# CRUVI.net
KiCad netlist of a schematic drawn in Altium Designer
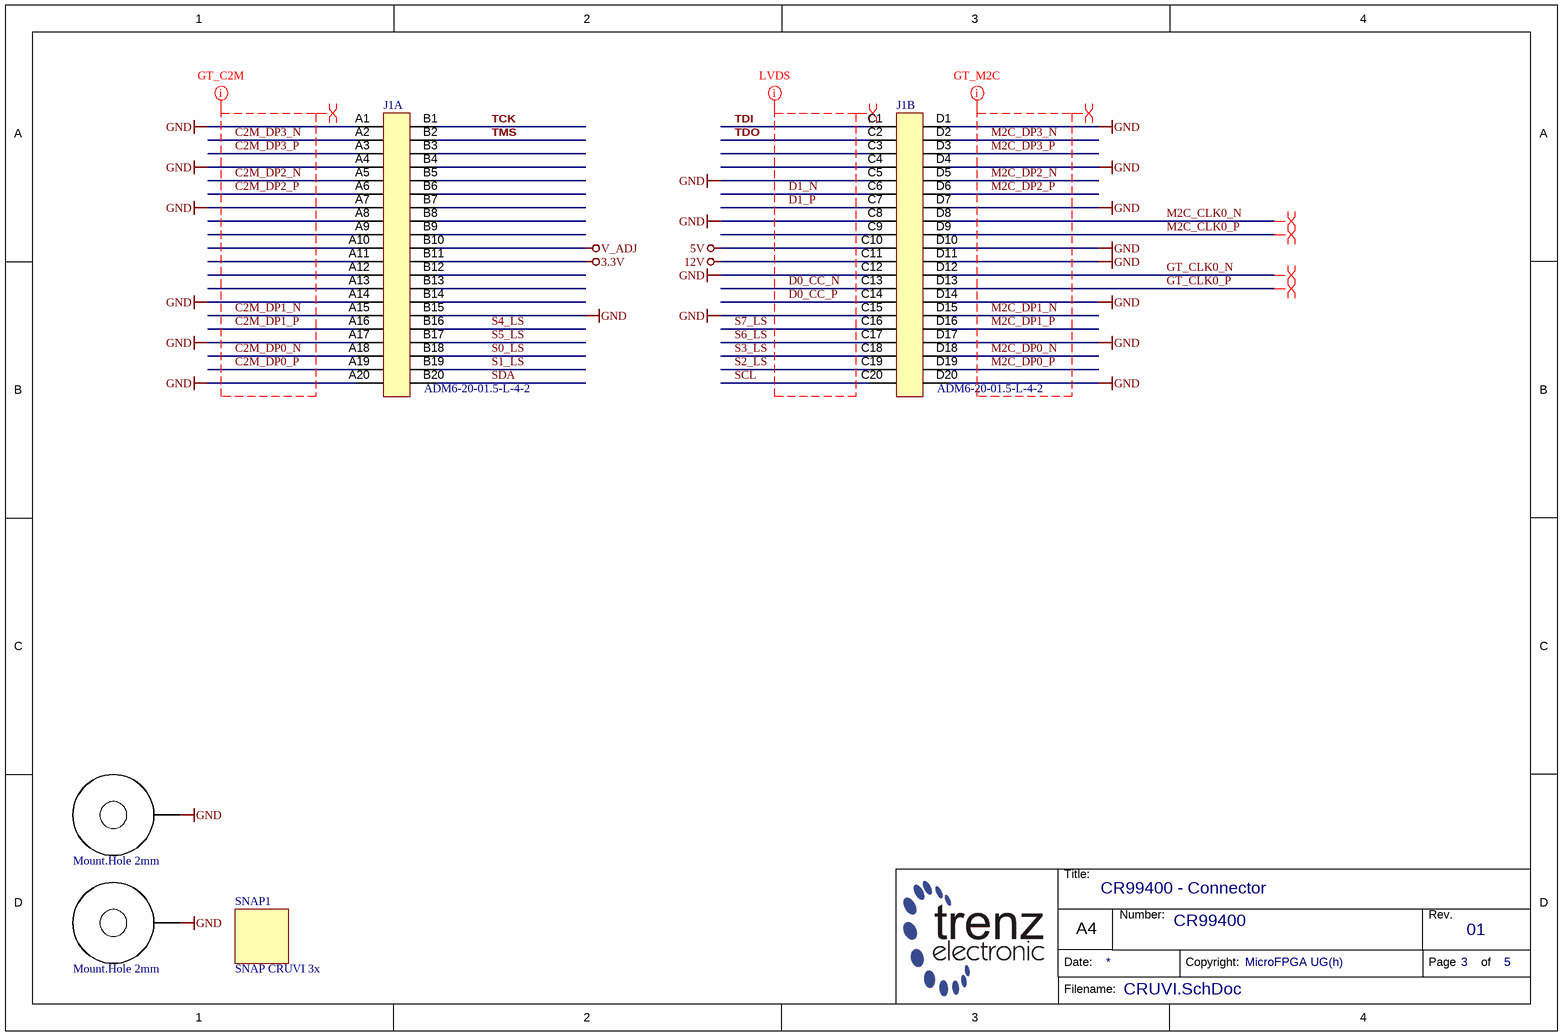
[diagram p0: CRUVI.SchDoc]

(export (version "E")
  (design (tool "Eeschema 10.0.6"))
  (components
    (comp (ref "H1")
      (value "Mount.Hole 2mm")
      (footprint "MHole2_2mm")
      (description "Mounting Hole 2mm Plated (Custom)")
      (libsource (lib "TE") (part "MHole"))
    )
    (comp (ref "H2")
      (value "Mount.Hole 2mm")
      (footprint "MHole2_2mm")
      (description "Mounting Hole 2mm Plated (Custom)")
      (libsource (lib "TE") (part "MHole"))
    )
    (comp (ref "J1")
      (value "ADM6-20-01.5-L-4-2")
      (footprint "ADM6-20-01.5-L-4-2")
      (fields (field (name "VOLTAGE") "155 VAC"))
      (libsource (lib "TE") (part "CON-20-A-D"))
    )
    (comp (ref "SNAP1")
      (value "SNAP CRUVI 3x")
      (footprint "CRUVI_3x_Snap")
      (description "SNAP for CRUVI 3x")
      (libsource (lib "TE") (part "DUMMY_NO_BOM"))
    )
  )
  (nets
    (net (code "1") (name "/C2M_DP0_N") (class "Default")
      (node (ref "J1") (pin "A18") (pinfunction "A18_A18") (pintype "passive"))
    )
    (net (code "2") (name "/C2M_DP0_P") (class "Default")
      (node (ref "J1") (pin "A19") (pinfunction "A19_A19") (pintype "passive"))
    )
    (net (code "3") (name "/C2M_DP1_N") (class "Default")
      (node (ref "J1") (pin "A15") (pinfunction "A15_A15") (pintype "passive"))
    )
    (net (code "4") (name "/C2M_DP1_P") (class "Default")
      (node (ref "J1") (pin "A16") (pinfunction "A16_A16") (pintype "passive"))
    )
    (net (code "5") (name "/C2M_DP2_N") (class "Default")
      (node (ref "J1") (pin "A5") (pinfunction "A5_A5") (pintype "passive"))
    )
    (net (code "6") (name "/C2M_DP2_P") (class "Default")
      (node (ref "J1") (pin "A6") (pinfunction "A6_A6") (pintype "passive"))
    )
    (net (code "7") (name "/C2M_DP3_N") (class "Default")
      (node (ref "J1") (pin "A2") (pinfunction "A2_A2") (pintype "passive"))
    )
    (net (code "8") (name "/C2M_DP3_P") (class "Default")
      (node (ref "J1") (pin "A3") (pinfunction "A3_A3") (pintype "passive"))
    )
    (net (code "9") (name "/D0_CC_N") (class "Default")
      (node (ref "J1") (pin "C13") (pinfunction "C13_C13") (pintype "passive"))
    )
    (net (code "10") (name "/D0_CC_P") (class "Default")
      (node (ref "J1") (pin "C14") (pinfunction "C14_C14") (pintype "passive"))
    )
    (net (code "11") (name "/D1_N") (class "Default")
      (node (ref "J1") (pin "C6") (pinfunction "C6_C6") (pintype "passive"))
    )
    (net (code "12") (name "/D1_P") (class "Default")
      (node (ref "J1") (pin "C7") (pinfunction "C7_C7") (pintype "passive"))
    )
    (net (code "13") (name "/GT_CLK0_N") (class "Default")
      (node (ref "J1") (pin "D12") (pinfunction "D12_D12") (pintype "passive"))
    )
    (net (code "14") (name "/GT_CLK0_P") (class "Default")
      (node (ref "J1") (pin "D13") (pinfunction "D13_D13") (pintype "passive"))
    )
    (net (code "15") (name "/M2C_CLK0_N") (class "Default")
      (node (ref "J1") (pin "D8") (pinfunction "D8_D8") (pintype "passive"))
    )
    (net (code "16") (name "/M2C_CLK0_P") (class "Default")
      (node (ref "J1") (pin "D9") (pinfunction "D9_D9") (pintype "passive"))
    )
    (net (code "17") (name "/M2C_DP0_N") (class "Default")
      (node (ref "J1") (pin "D18") (pinfunction "D18_D18") (pintype "passive"))
    )
    (net (code "18") (name "/M2C_DP0_P") (class "Default")
      (node (ref "J1") (pin "D19") (pinfunction "D19_D19") (pintype "passive"))
    )
    (net (code "19") (name "/M2C_DP1_N") (class "Default")
      (node (ref "J1") (pin "D15") (pinfunction "D15_D15") (pintype "passive"))
    )
    (net (code "20") (name "/M2C_DP1_P") (class "Default")
      (node (ref "J1") (pin "D16") (pinfunction "D16_D16") (pintype "passive"))
    )
    (net (code "21") (name "/M2C_DP2_N") (class "Default")
      (node (ref "J1") (pin "D5") (pinfunction "D5_D5") (pintype "passive"))
    )
    (net (code "22") (name "/M2C_DP2_P") (class "Default")
      (node (ref "J1") (pin "D6") (pinfunction "D6_D6") (pintype "passive"))
    )
    (net (code "23") (name "/M2C_DP3_N") (class "Default")
      (node (ref "J1") (pin "D2") (pinfunction "D2_D2") (pintype "passive"))
    )
    (net (code "24") (name "/M2C_DP3_P") (class "Default")
      (node (ref "J1") (pin "D3") (pinfunction "D3_D3") (pintype "passive"))
    )
    (net (code "25") (name "/S0_LS") (class "Default")
      (node (ref "J1") (pin "B18") (pinfunction "B18_B18") (pintype "passive"))
    )
    (net (code "26") (name "/S1_LS") (class "Default")
      (node (ref "J1") (pin "B19") (pinfunction "B19_B19") (pintype "passive"))
    )
    (net (code "27") (name "/S2_LS") (class "Default")
      (node (ref "J1") (pin "C19") (pinfunction "C19_C19") (pintype "passive"))
    )
    (net (code "28") (name "/S3_LS") (class "Default")
      (node (ref "J1") (pin "C18") (pinfunction "C18_C18") (pintype "passive"))
    )
    (net (code "29") (name "/S4_LS") (class "Default")
      (node (ref "J1") (pin "B16") (pinfunction "B16_B16") (pintype "passive"))
    )
    (net (code "30") (name "/S5_LS") (class "Default")
      (node (ref "J1") (pin "B17") (pinfunction "B17_B17") (pintype "passive"))
    )
    (net (code "31") (name "/S6_LS") (class "Default")
      (node (ref "J1") (pin "C17") (pinfunction "C17_C17") (pintype "passive"))
    )
    (net (code "32") (name "/S7_LS") (class "Default")
      (node (ref "J1") (pin "C16") (pinfunction "C16_C16") (pintype "passive"))
    )
    (net (code "33") (name "/SCL") (class "Default")
      (node (ref "J1") (pin "C20") (pinfunction "C20_C20") (pintype "passive"))
    )
    (net (code "34") (name "/SDA") (class "Default")
      (node (ref "J1") (pin "B20") (pinfunction "B20_B20") (pintype "passive"))
    )
    (net (code "35") (name "/TCK") (class "Default")
      (node (ref "J1") (pin "B1") (pinfunction "B1_B1") (pintype "passive"))
    )
    (net (code "36") (name "/TDI") (class "Default")
      (node (ref "J1") (pin "C1") (pinfunction "C1_C1") (pintype "passive"))
    )
    (net (code "37") (name "/TDO") (class "Default")
      (node (ref "J1") (pin "C2") (pinfunction "C2_C2") (pintype "passive"))
    )
    (net (code "38") (name "/TMS") (class "Default")
      (node (ref "J1") (pin "B2") (pinfunction "B2_B2") (pintype "passive"))
    )
    (net (code "39") (name "3.3V") (class "Default")
      (node (ref "J1") (pin "B11") (pinfunction "B11_B11") (pintype "passive"))
    )
    (net (code "40") (name "5V") (class "Default")
      (node (ref "J1") (pin "C10") (pinfunction "C10_C10") (pintype "passive"))
    )
    (net (code "41") (name "12V") (class "Default")
      (node (ref "J1") (pin "C11") (pinfunction "C11_C11") (pintype "passive"))
    )
    (net (code "42") (name "GND") (class "Default")
      (node (ref "H1") (pin "1") (pinfunction "1_1") (pintype "passive"))
      (node (ref "H2") (pin "1") (pinfunction "1_1") (pintype "passive"))
      (node (ref "J1") (pin "A1") (pinfunction "A1_A1") (pintype "passive"))
      (node (ref "J1") (pin "A14") (pinfunction "A14_A14") (pintype "passive"))
      (node (ref "J1") (pin "A17") (pinfunction "A17_A17") (pintype "passive"))
      (node (ref "J1") (pin "A20") (pinfunction "A20_A20") (pintype "passive"))
      (node (ref "J1") (pin "A4") (pinfunction "A4_A4") (pintype "passive"))
      (node (ref "J1") (pin "A7") (pinfunction "A7_A7") (pintype "passive"))
      (node (ref "J1") (pin "B15") (pinfunction "B15_B15") (pintype "passive"))
      (node (ref "J1") (pin "C12") (pinfunction "C12_C12") (pintype "passive"))
      (node (ref "J1") (pin "C15") (pinfunction "C15_C15") (pintype "passive"))
      (node (ref "J1") (pin "C5") (pinfunction "C5_C5") (pintype "passive"))
      (node (ref "J1") (pin "C8") (pinfunction "C8_C8") (pintype "passive"))
      (node (ref "J1") (pin "D1") (pinfunction "D1_D1") (pintype "passive"))
      (node (ref "J1") (pin "D10") (pinfunction "D10_D10") (pintype "passive"))
      (node (ref "J1") (pin "D11") (pinfunction "D11_D11") (pintype "passive"))
      (node (ref "J1") (pin "D14") (pinfunction "D14_D14") (pintype "passive"))
      (node (ref "J1") (pin "D17") (pinfunction "D17_D17") (pintype "passive"))
      (node (ref "J1") (pin "D20") (pinfunction "D20_D20") (pintype "passive"))
      (node (ref "J1") (pin "D4") (pinfunction "D4_D4") (pintype "passive"))
      (node (ref "J1") (pin "D7") (pinfunction "D7_D7") (pintype "passive"))
    )
    (net (code "43") (name "V_ADJ") (class "Default")
      (node (ref "J1") (pin "B10") (pinfunction "B10_B10") (pintype "passive"))
    )
    (net (code "44") (name "unconnected-(J1-PadA8)") (class "Default")
      (node (ref "J1") (pin "A8") (pinfunction "A8_A8") (pintype "passive"))
    )
    (net (code "45") (name "unconnected-(J1-PadA9)") (class "Default")
      (node (ref "J1") (pin "A9") (pinfunction "A9_A9") (pintype "passive"))
    )
    (net (code "46") (name "unconnected-(J1-PadA10)") (class "Default")
      (node (ref "J1") (pin "A10") (pinfunction "A10_A10") (pintype "passive"))
    )
    (net (code "47") (name "unconnected-(J1-PadA11)") (class "Default")
      (node (ref "J1") (pin "A11") (pinfunction "A11_A11") (pintype "passive"))
    )
    (net (code "48") (name "unconnected-(J1-PadA12)") (class "Default")
      (node (ref "J1") (pin "A12") (pinfunction "A12_A12") (pintype "passive"))
    )
    (net (code "49") (name "unconnected-(J1-PadA13)") (class "Default")
      (node (ref "J1") (pin "A13") (pinfunction "A13_A13") (pintype "passive"))
    )
    (net (code "50") (name "unconnected-(J1-PadB3)") (class "Default")
      (node (ref "J1") (pin "B3") (pinfunction "B3_B3") (pintype "passive"))
    )
    (net (code "51") (name "unconnected-(J1-PadB4)") (class "Default")
      (node (ref "J1") (pin "B4") (pinfunction "B4_B4") (pintype "passive"))
    )
    (net (code "52") (name "unconnected-(J1-PadB5)") (class "Default")
      (node (ref "J1") (pin "B5") (pinfunction "B5_B5") (pintype "passive"))
    )
    (net (code "53") (name "unconnected-(J1-PadB6)") (class "Default")
      (node (ref "J1") (pin "B6") (pinfunction "B6_B6") (pintype "passive"))
    )
    (net (code "54") (name "unconnected-(J1-PadB7)") (class "Default")
      (node (ref "J1") (pin "B7") (pinfunction "B7_B7") (pintype "passive"))
    )
    (net (code "55") (name "unconnected-(J1-PadB8)") (class "Default")
      (node (ref "J1") (pin "B8") (pinfunction "B8_B8") (pintype "passive"))
    )
    (net (code "56") (name "unconnected-(J1-PadB9)") (class "Default")
      (node (ref "J1") (pin "B9") (pinfunction "B9_B9") (pintype "passive"))
    )
    (net (code "57") (name "unconnected-(J1-PadB12)") (class "Default")
      (node (ref "J1") (pin "B12") (pinfunction "B12_B12") (pintype "passive"))
    )
    (net (code "58") (name "unconnected-(J1-PadB13)") (class "Default")
      (node (ref "J1") (pin "B13") (pinfunction "B13_B13") (pintype "passive"))
    )
    (net (code "59") (name "unconnected-(J1-PadB14)") (class "Default")
      (node (ref "J1") (pin "B14") (pinfunction "B14_B14") (pintype "passive"))
    )
    (net (code "60") (name "unconnected-(J1-PadC3)") (class "Default")
      (node (ref "J1") (pin "C3") (pinfunction "C3_C3") (pintype "passive"))
    )
    (net (code "61") (name "unconnected-(J1-PadC4)") (class "Default")
      (node (ref "J1") (pin "C4") (pinfunction "C4_C4") (pintype "passive"))
    )
    (net (code "62") (name "unconnected-(J1-PadC9)") (class "Default")
      (node (ref "J1") (pin "C9") (pinfunction "C9_C9") (pintype "passive"))
    )
  )
)
